# 17.net
KiCad netlist of a schematic drawn in EAGLE
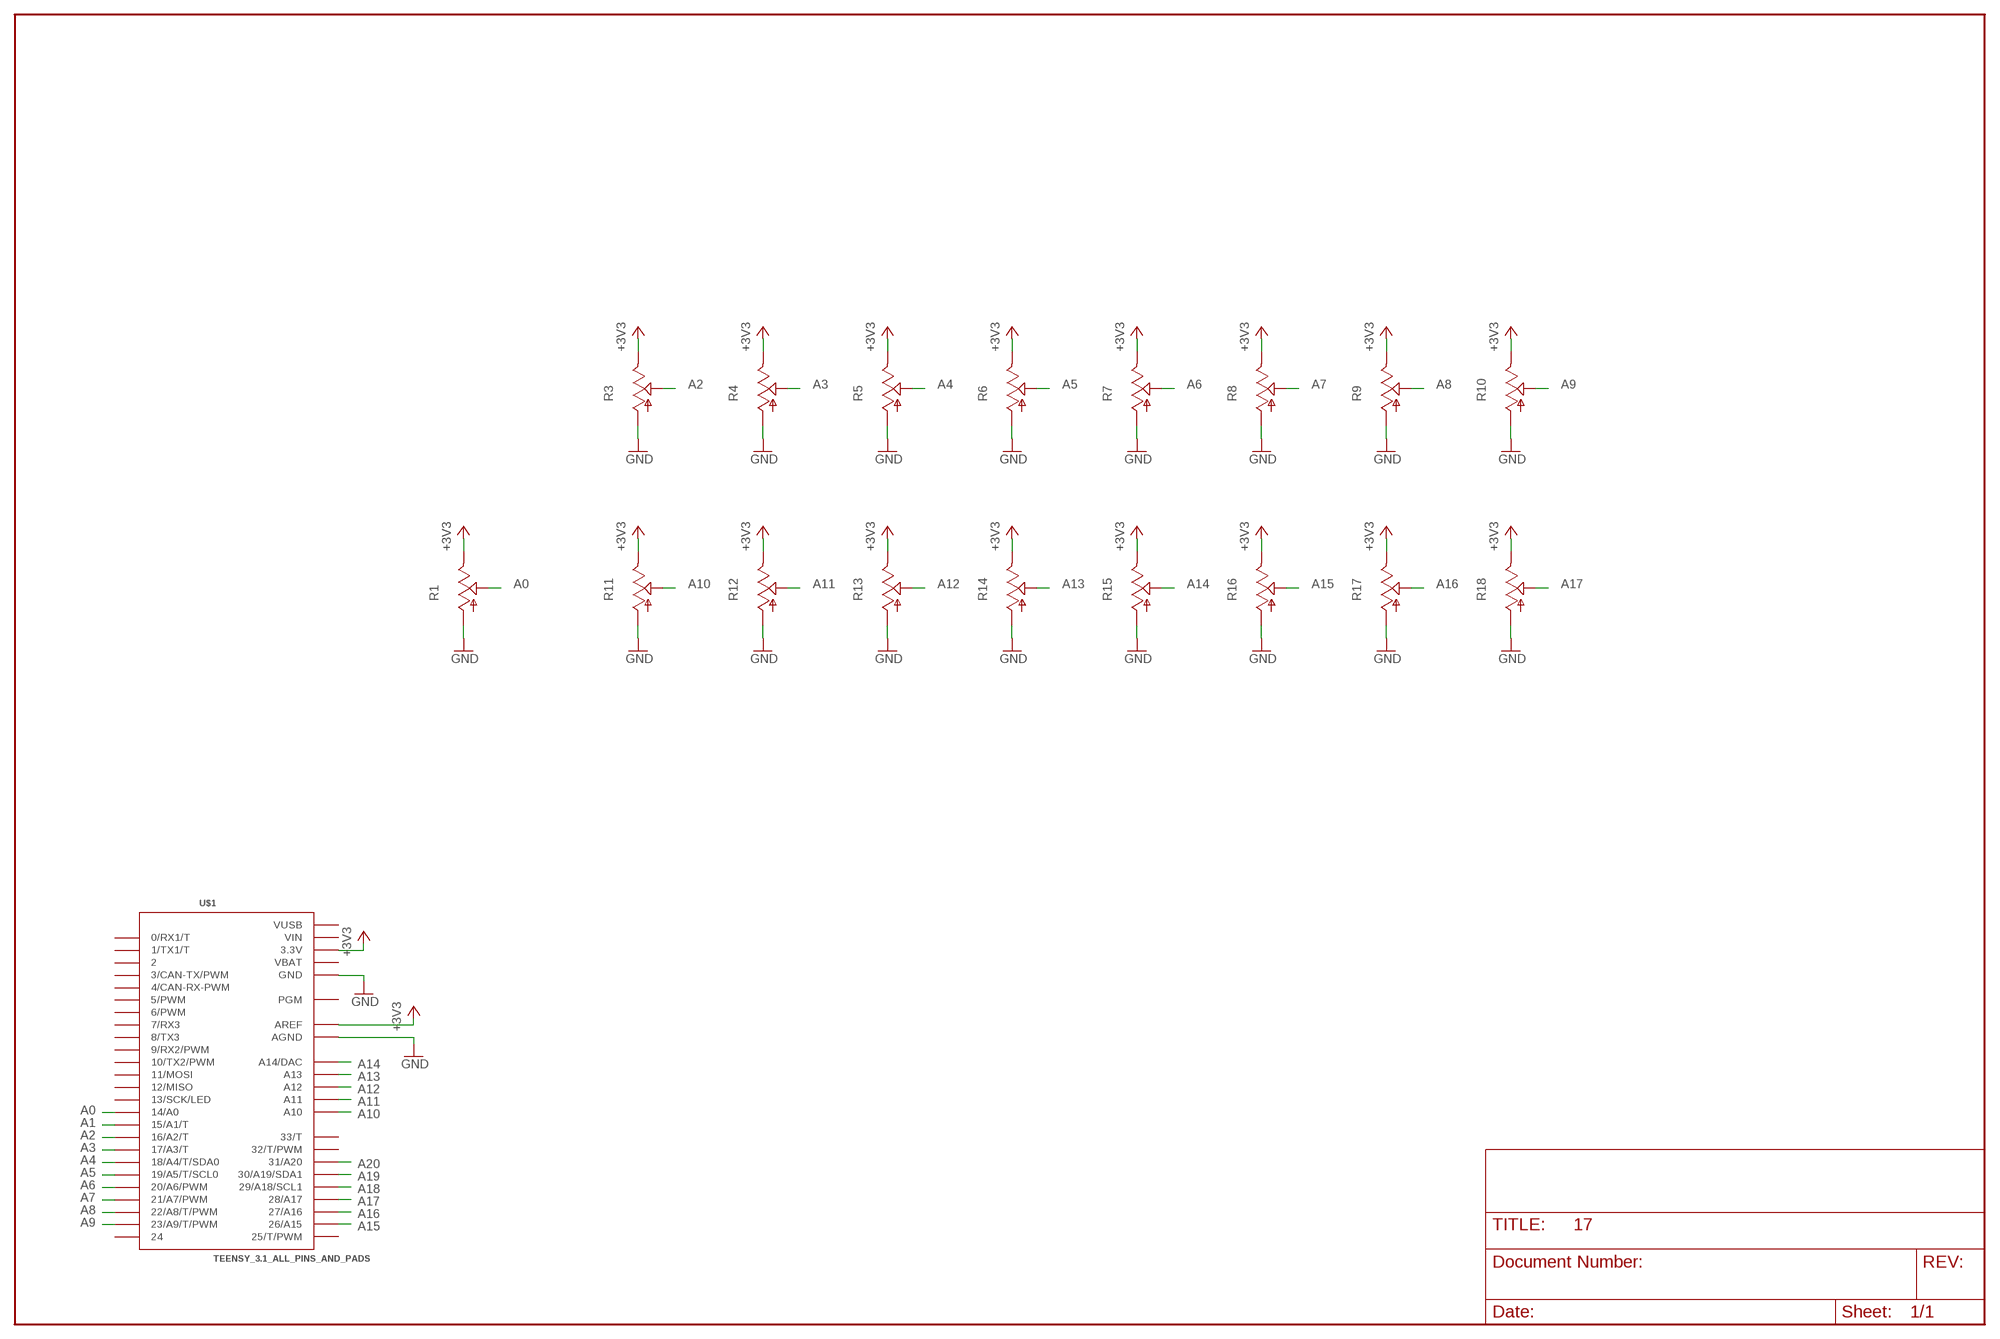
[diagram p0: schematic, sheet 1]

(export (version "E")
  (design (tool "Eeschema 10.0.6"))
  (components
    (comp (ref "R1")
      (value "SHAPES_POT-ALPS_POT_USVERTICAL_PS")
      (footprint "eagle-import:SHAPES_POT-ALPS_ALPS_POT_VERTICAL_PS")
      (libsource (lib "eagle-import") (part "SHAPES_POT-ALPS_POT_USVERTICAL_PS"))
    )
    (comp (ref "R3")
      (value "SHAPES_POT-ALPS_POT_USVERTICAL_PS")
      (footprint "eagle-import:SHAPES_POT-ALPS_ALPS_POT_VERTICAL_PS")
      (libsource (lib "eagle-import") (part "SHAPES_POT-ALPS_POT_USVERTICAL_PS"))
    )
    (comp (ref "R4")
      (value "SHAPES_POT-ALPS_POT_USVERTICAL_PS")
      (footprint "eagle-import:SHAPES_POT-ALPS_ALPS_POT_VERTICAL_PS")
      (libsource (lib "eagle-import") (part "SHAPES_POT-ALPS_POT_USVERTICAL_PS"))
    )
    (comp (ref "R5")
      (value "SHAPES_POT-ALPS_POT_USVERTICAL_PS")
      (footprint "eagle-import:SHAPES_POT-ALPS_ALPS_POT_VERTICAL_PS")
      (libsource (lib "eagle-import") (part "SHAPES_POT-ALPS_POT_USVERTICAL_PS"))
    )
    (comp (ref "R6")
      (value "SHAPES_POT-ALPS_POT_USVERTICAL_PS")
      (footprint "eagle-import:SHAPES_POT-ALPS_ALPS_POT_VERTICAL_PS")
      (libsource (lib "eagle-import") (part "SHAPES_POT-ALPS_POT_USVERTICAL_PS"))
    )
    (comp (ref "R7")
      (value "SHAPES_POT-ALPS_POT_USVERTICAL_PS")
      (footprint "eagle-import:SHAPES_POT-ALPS_ALPS_POT_VERTICAL_PS")
      (libsource (lib "eagle-import") (part "SHAPES_POT-ALPS_POT_USVERTICAL_PS"))
    )
    (comp (ref "R8")
      (value "SHAPES_POT-ALPS_POT_USVERTICAL_PS")
      (footprint "eagle-import:SHAPES_POT-ALPS_ALPS_POT_VERTICAL_PS")
      (libsource (lib "eagle-import") (part "SHAPES_POT-ALPS_POT_USVERTICAL_PS"))
    )
    (comp (ref "R9")
      (value "SHAPES_POT-ALPS_POT_USVERTICAL_PS")
      (footprint "eagle-import:SHAPES_POT-ALPS_ALPS_POT_VERTICAL_PS")
      (libsource (lib "eagle-import") (part "SHAPES_POT-ALPS_POT_USVERTICAL_PS"))
    )
    (comp (ref "R10")
      (value "SHAPES_POT-ALPS_POT_USVERTICAL_PS")
      (footprint "eagle-import:SHAPES_POT-ALPS_ALPS_POT_VERTICAL_PS")
      (libsource (lib "eagle-import") (part "SHAPES_POT-ALPS_POT_USVERTICAL_PS"))
    )
    (comp (ref "R11")
      (value "SHAPES_POT-ALPS_POT_USVERTICAL_PS")
      (footprint "eagle-import:SHAPES_POT-ALPS_ALPS_POT_VERTICAL_PS")
      (libsource (lib "eagle-import") (part "SHAPES_POT-ALPS_POT_USVERTICAL_PS"))
    )
    (comp (ref "R12")
      (value "SHAPES_POT-ALPS_POT_USVERTICAL_PS")
      (footprint "eagle-import:SHAPES_POT-ALPS_ALPS_POT_VERTICAL_PS")
      (libsource (lib "eagle-import") (part "SHAPES_POT-ALPS_POT_USVERTICAL_PS"))
    )
    (comp (ref "R13")
      (value "SHAPES_POT-ALPS_POT_USVERTICAL_PS")
      (footprint "eagle-import:SHAPES_POT-ALPS_ALPS_POT_VERTICAL_PS")
      (libsource (lib "eagle-import") (part "SHAPES_POT-ALPS_POT_USVERTICAL_PS"))
    )
    (comp (ref "R14")
      (value "SHAPES_POT-ALPS_POT_USVERTICAL_PS")
      (footprint "eagle-import:SHAPES_POT-ALPS_ALPS_POT_VERTICAL_PS")
      (libsource (lib "eagle-import") (part "SHAPES_POT-ALPS_POT_USVERTICAL_PS"))
    )
    (comp (ref "R15")
      (value "SHAPES_POT-ALPS_POT_USVERTICAL_PS")
      (footprint "eagle-import:SHAPES_POT-ALPS_ALPS_POT_VERTICAL_PS")
      (libsource (lib "eagle-import") (part "SHAPES_POT-ALPS_POT_USVERTICAL_PS"))
    )
    (comp (ref "R16")
      (value "SHAPES_POT-ALPS_POT_USVERTICAL_PS")
      (footprint "eagle-import:SHAPES_POT-ALPS_ALPS_POT_VERTICAL_PS")
      (libsource (lib "eagle-import") (part "SHAPES_POT-ALPS_POT_USVERTICAL_PS"))
    )
    (comp (ref "R17")
      (value "SHAPES_POT-ALPS_POT_USVERTICAL_PS")
      (footprint "eagle-import:SHAPES_POT-ALPS_ALPS_POT_VERTICAL_PS")
      (libsource (lib "eagle-import") (part "SHAPES_POT-ALPS_POT_USVERTICAL_PS"))
    )
    (comp (ref "R18")
      (value "SHAPES_POT-ALPS_POT_USVERTICAL_PS")
      (footprint "eagle-import:SHAPES_POT-ALPS_ALPS_POT_VERTICAL_PS")
      (libsource (lib "eagle-import") (part "SHAPES_POT-ALPS_POT_USVERTICAL_PS"))
    )
    (comp (ref "U$1")
      (value "TEENSY_3.1_ALL_PINS_AND_PADS")
      (footprint "eagle-import:TEENSY_3.1_ALLPINS")
      (libsource (lib "eagle-import") (part "TEENSY_3.1_ALL_PINS_AND_PADS"))
    )
  )
  (nets
    (net (code "1") (name "+3V3") (class "Default")
      (node (ref "R1") (pin "P$1") (pinfunction "E_P$1") (pintype "passive"))
      (node (ref "R10") (pin "P$1") (pinfunction "E_P$1") (pintype "passive"))
      (node (ref "R11") (pin "P$1") (pinfunction "E_P$1") (pintype "passive"))
      (node (ref "R12") (pin "P$1") (pinfunction "E_P$1") (pintype "passive"))
      (node (ref "R13") (pin "P$1") (pinfunction "E_P$1") (pintype "passive"))
      (node (ref "R14") (pin "P$1") (pinfunction "E_P$1") (pintype "passive"))
      (node (ref "R15") (pin "P$1") (pinfunction "E_P$1") (pintype "passive"))
      (node (ref "R16") (pin "P$1") (pinfunction "E_P$1") (pintype "passive"))
      (node (ref "R17") (pin "P$1") (pinfunction "E_P$1") (pintype "passive"))
      (node (ref "R18") (pin "P$1") (pinfunction "E_P$1") (pintype "passive"))
      (node (ref "R3") (pin "P$1") (pinfunction "E_P$1") (pintype "passive"))
      (node (ref "R4") (pin "P$1") (pinfunction "E_P$1") (pintype "passive"))
      (node (ref "R5") (pin "P$1") (pinfunction "E_P$1") (pintype "passive"))
      (node (ref "R6") (pin "P$1") (pinfunction "E_P$1") (pintype "passive"))
      (node (ref "R7") (pin "P$1") (pinfunction "E_P$1") (pintype "passive"))
      (node (ref "R8") (pin "P$1") (pinfunction "E_P$1") (pintype "passive"))
      (node (ref "R9") (pin "P$1") (pinfunction "E_P$1") (pintype "passive"))
      (node (ref "U$1") (pin "3.3V") (pinfunction "3.3V_3.3V") (pintype "power_in"))
      (node (ref "U$1") (pin "3.3V1") (pinfunction "3.3V_3.3V1") (pintype "power_in"))
      (node (ref "U$1") (pin "3.3V2") (pinfunction "3.3V_3.3V2") (pintype "power_in"))
      (node (ref "U$1") (pin "AREF") (pinfunction "AREF_AREF") (pintype "power_in"))
    )
    (net (code "2") (name "/A0") (class "Default")
      (node (ref "R1") (pin "P$2") (pinfunction "S_P$2") (pintype "passive"))
      (node (ref "U$1") (pin "14/A0") (pinfunction "14/A0_14/A0") (pintype "bidirectional"))
    )
    (net (code "3") (name "/A1") (class "Default")
      (node (ref "U$1") (pin "15/A1") (pinfunction "15/A1/T_15/A1") (pintype "bidirectional"))
    )
    (net (code "4") (name "/A2") (class "Default")
      (node (ref "R3") (pin "P$2") (pinfunction "S_P$2") (pintype "passive"))
      (node (ref "U$1") (pin "16/A2") (pinfunction "16/A2/T_16/A2") (pintype "bidirectional"))
    )
    (net (code "5") (name "/A3") (class "Default")
      (node (ref "R4") (pin "P$2") (pinfunction "S_P$2") (pintype "passive"))
      (node (ref "U$1") (pin "17/A3") (pinfunction "17/A3/T_17/A3") (pintype "bidirectional"))
    )
    (net (code "6") (name "/A4") (class "Default")
      (node (ref "R5") (pin "P$2") (pinfunction "S_P$2") (pintype "passive"))
      (node (ref "U$1") (pin "18/A4") (pinfunction "18/A4/T/SDA0_18/A4") (pintype "bidirectional"))
    )
    (net (code "7") (name "/A5") (class "Default")
      (node (ref "R6") (pin "P$2") (pinfunction "S_P$2") (pintype "passive"))
      (node (ref "U$1") (pin "19/A5") (pinfunction "19/A5/T/SCL0_19/A5") (pintype "bidirectional"))
    )
    (net (code "8") (name "/A6") (class "Default")
      (node (ref "R7") (pin "P$2") (pinfunction "S_P$2") (pintype "passive"))
      (node (ref "U$1") (pin "20/A6") (pinfunction "20/A6/PWM_20/A6") (pintype "bidirectional"))
    )
    (net (code "9") (name "/A7") (class "Default")
      (node (ref "R8") (pin "P$2") (pinfunction "S_P$2") (pintype "passive"))
      (node (ref "U$1") (pin "21/A7") (pinfunction "21/A7/PWM_21/A7") (pintype "bidirectional"))
    )
    (net (code "10") (name "/A8") (class "Default")
      (node (ref "R9") (pin "P$2") (pinfunction "S_P$2") (pintype "passive"))
      (node (ref "U$1") (pin "22/A8") (pinfunction "22/A8/T/PWM_22/A8") (pintype "bidirectional"))
    )
    (net (code "11") (name "/A9") (class "Default")
      (node (ref "R10") (pin "P$2") (pinfunction "S_P$2") (pintype "passive"))
      (node (ref "U$1") (pin "23/A9") (pinfunction "23/A9/T/PWM_23/A9") (pintype "bidirectional"))
    )
    (net (code "12") (name "/A10") (class "Default")
      (node (ref "R11") (pin "P$2") (pinfunction "S_P$2") (pintype "passive"))
      (node (ref "U$1") (pin "A10") (pinfunction "A10_A10") (pintype "bidirectional"))
    )
    (net (code "13") (name "/A11") (class "Default")
      (node (ref "R12") (pin "P$2") (pinfunction "S_P$2") (pintype "passive"))
      (node (ref "U$1") (pin "A11") (pinfunction "A11_A11") (pintype "bidirectional"))
    )
    (net (code "14") (name "/A12") (class "Default")
      (node (ref "R13") (pin "P$2") (pinfunction "S_P$2") (pintype "passive"))
      (node (ref "U$1") (pin "A12") (pinfunction "A12_A12") (pintype "bidirectional"))
    )
    (net (code "15") (name "/A13") (class "Default")
      (node (ref "R14") (pin "P$2") (pinfunction "S_P$2") (pintype "passive"))
      (node (ref "U$1") (pin "A13") (pinfunction "A13_A13") (pintype "bidirectional"))
    )
    (net (code "16") (name "/A14") (class "Default")
      (node (ref "R15") (pin "P$2") (pinfunction "S_P$2") (pintype "passive"))
      (node (ref "U$1") (pin "A14") (pinfunction "A14/DAC_A14") (pintype "bidirectional"))
    )
    (net (code "17") (name "/A15") (class "Default")
      (node (ref "R16") (pin "P$2") (pinfunction "S_P$2") (pintype "passive"))
      (node (ref "U$1") (pin "26") (pinfunction "26/A15_26") (pintype "bidirectional"))
    )
    (net (code "18") (name "/A16") (class "Default")
      (node (ref "R17") (pin "P$2") (pinfunction "S_P$2") (pintype "passive"))
      (node (ref "U$1") (pin "27") (pinfunction "27/A16_27") (pintype "bidirectional"))
    )
    (net (code "19") (name "/A17") (class "Default")
      (node (ref "R18") (pin "P$2") (pinfunction "S_P$2") (pintype "passive"))
      (node (ref "U$1") (pin "28") (pinfunction "28/A17_28") (pintype "bidirectional"))
    )
    (net (code "20") (name "/A18") (class "Default")
      (node (ref "U$1") (pin "29") (pinfunction "29/A18/SCL1_29") (pintype "bidirectional"))
    )
    (net (code "21") (name "/A19") (class "Default")
      (node (ref "U$1") (pin "30") (pinfunction "30/A19/SDA1_30") (pintype "bidirectional"))
    )
    (net (code "22") (name "/A20") (class "Default")
      (node (ref "U$1") (pin "31") (pinfunction "31/A20_31") (pintype "bidirectional"))
    )
    (net (code "23") (name "/VBAT") (class "Default")
      (node (ref "U$1") (pin "VBAT") (pinfunction "VBAT_VBAT") (pintype "power_in"))
    )
    (net (code "24") (name "/VIN") (class "Default")
      (node (ref "U$1") (pin "VIN") (pinfunction "VIN_VIN") (pintype "power_in"))
    )
    (net (code "25") (name "/VUSB") (class "Default")
      (node (ref "U$1") (pin "VUSB") (pinfunction "VUSB_VUSB") (pintype "power_in"))
    )
    (net (code "26") (name "GND") (class "Default")
      (node (ref "R1") (pin "P$3") (pinfunction "A_P$3") (pintype "passive"))
      (node (ref "R10") (pin "P$3") (pinfunction "A_P$3") (pintype "passive"))
      (node (ref "R11") (pin "P$3") (pinfunction "A_P$3") (pintype "passive"))
      (node (ref "R12") (pin "P$3") (pinfunction "A_P$3") (pintype "passive"))
      (node (ref "R13") (pin "P$3") (pinfunction "A_P$3") (pintype "passive"))
      (node (ref "R14") (pin "P$3") (pinfunction "A_P$3") (pintype "passive"))
      (node (ref "R15") (pin "P$3") (pinfunction "A_P$3") (pintype "passive"))
      (node (ref "R16") (pin "P$3") (pinfunction "A_P$3") (pintype "passive"))
      (node (ref "R17") (pin "P$3") (pinfunction "A_P$3") (pintype "passive"))
      (node (ref "R18") (pin "P$3") (pinfunction "A_P$3") (pintype "passive"))
      (node (ref "R3") (pin "P$3") (pinfunction "A_P$3") (pintype "passive"))
      (node (ref "R4") (pin "P$3") (pinfunction "A_P$3") (pintype "passive"))
      (node (ref "R5") (pin "P$3") (pinfunction "A_P$3") (pintype "passive"))
      (node (ref "R6") (pin "P$3") (pinfunction "A_P$3") (pintype "passive"))
      (node (ref "R7") (pin "P$3") (pinfunction "A_P$3") (pintype "passive"))
      (node (ref "R8") (pin "P$3") (pinfunction "A_P$3") (pintype "passive"))
      (node (ref "R9") (pin "P$3") (pinfunction "A_P$3") (pintype "passive"))
      (node (ref "U$1") (pin "AGND") (pinfunction "AGND_AGND") (pintype "power_in"))
      (node (ref "U$1") (pin "GND") (pinfunction "GND_GND") (pintype "power_in"))
      (node (ref "U$1") (pin "GND1") (pinfunction "GND_GND1") (pintype "power_in"))
      (node (ref "U$1") (pin "GND2") (pinfunction "GND_GND2") (pintype "power_in"))
    )
    (net (code "27") (name "unconnected-(U$1-0{slash}RX1{slash}T-Pad0)") (class "Default")
      (node (ref "U$1") (pin "0") (pinfunction "0/RX1/T_0") (pintype "bidirectional"))
    )
    (net (code "28") (name "unconnected-(U$1-1{slash}TX1{slash}T-Pad1)") (class "Default")
      (node (ref "U$1") (pin "1") (pinfunction "1/TX1/T_1") (pintype "bidirectional"))
    )
    (net (code "29") (name "unconnected-(U$1-3{slash}CAN-TX{slash}PWM-Pad3)") (class "Default")
      (node (ref "U$1") (pin "3") (pinfunction "3/CAN-TX/PWM_3") (pintype "bidirectional"))
    )
    (net (code "30") (name "unconnected-(U$1-4{slash}CAN-RX-PWM-Pad4)") (class "Default")
      (node (ref "U$1") (pin "4") (pinfunction "4/CAN-RX-PWM_4") (pintype "bidirectional"))
    )
    (net (code "31") (name "unconnected-(U$1-5{slash}PWM-Pad5)") (class "Default")
      (node (ref "U$1") (pin "5") (pinfunction "5/PWM_5") (pintype "bidirectional"))
    )
    (net (code "32") (name "unconnected-(U$1-6{slash}PWM-Pad6)") (class "Default")
      (node (ref "U$1") (pin "6") (pinfunction "6/PWM_6") (pintype "bidirectional"))
    )
    (net (code "33") (name "unconnected-(U$1-7{slash}RX3-Pad7)") (class "Default")
      (node (ref "U$1") (pin "7") (pinfunction "7/RX3_7") (pintype "bidirectional"))
    )
    (net (code "34") (name "unconnected-(U$1-8{slash}TX3-Pad8)") (class "Default")
      (node (ref "U$1") (pin "8") (pinfunction "8/TX3_8") (pintype "bidirectional"))
    )
    (net (code "35") (name "unconnected-(U$1-9{slash}RX2{slash}PWM-Pad9)") (class "Default")
      (node (ref "U$1") (pin "9") (pinfunction "9/RX2/PWM_9") (pintype "bidirectional"))
    )
    (net (code "36") (name "unconnected-(U$1-10{slash}TX2{slash}PWM-Pad10)") (class "Default")
      (node (ref "U$1") (pin "10") (pinfunction "10/TX2/PWM_10") (pintype "bidirectional"))
    )
    (net (code "37") (name "unconnected-(U$1-11{slash}MOSI-Pad11)") (class "Default")
      (node (ref "U$1") (pin "11") (pinfunction "11/MOSI_11") (pintype "bidirectional"))
    )
    (net (code "38") (name "unconnected-(U$1-12{slash}MISO-Pad12)") (class "Default")
      (node (ref "U$1") (pin "12") (pinfunction "12/MISO_12") (pintype "bidirectional"))
    )
    (net (code "39") (name "unconnected-(U$1-13{slash}SCK{slash}LED-Pad13)") (class "Default")
      (node (ref "U$1") (pin "13") (pinfunction "13/SCK/LED_13") (pintype "bidirectional"))
    )
    (net (code "40") (name "unconnected-(U$1-25{slash}T{slash}PWM-Pad25)") (class "Default")
      (node (ref "U$1") (pin "25") (pinfunction "25/T/PWM_25") (pintype "bidirectional"))
    )
    (net (code "41") (name "unconnected-(U$1-32{slash}T{slash}PWM-Pad32)") (class "Default")
      (node (ref "U$1") (pin "32") (pinfunction "32/T/PWM_32") (pintype "bidirectional"))
    )
    (net (code "42") (name "unconnected-(U$1-33{slash}T-Pad33)") (class "Default")
      (node (ref "U$1") (pin "33") (pinfunction "33/T_33") (pintype "bidirectional"))
    )
    (net (code "43") (name "unconnected-(U$1-Pad2)") (class "Default")
      (node (ref "U$1") (pin "2") (pinfunction "2_2") (pintype "bidirectional"))
    )
    (net (code "44") (name "unconnected-(U$1-Pad24)") (class "Default")
      (node (ref "U$1") (pin "24") (pinfunction "24_24") (pintype "bidirectional"))
    )
    (net (code "45") (name "unconnected-(U$1-PadPGM)") (class "Default")
      (node (ref "U$1") (pin "PGM") (pinfunction "PGM_PGM") (pintype "bidirectional"))
    )
  )
)
